# 220_small.net
KiCad netlist of a schematic drawn in Altium Designer
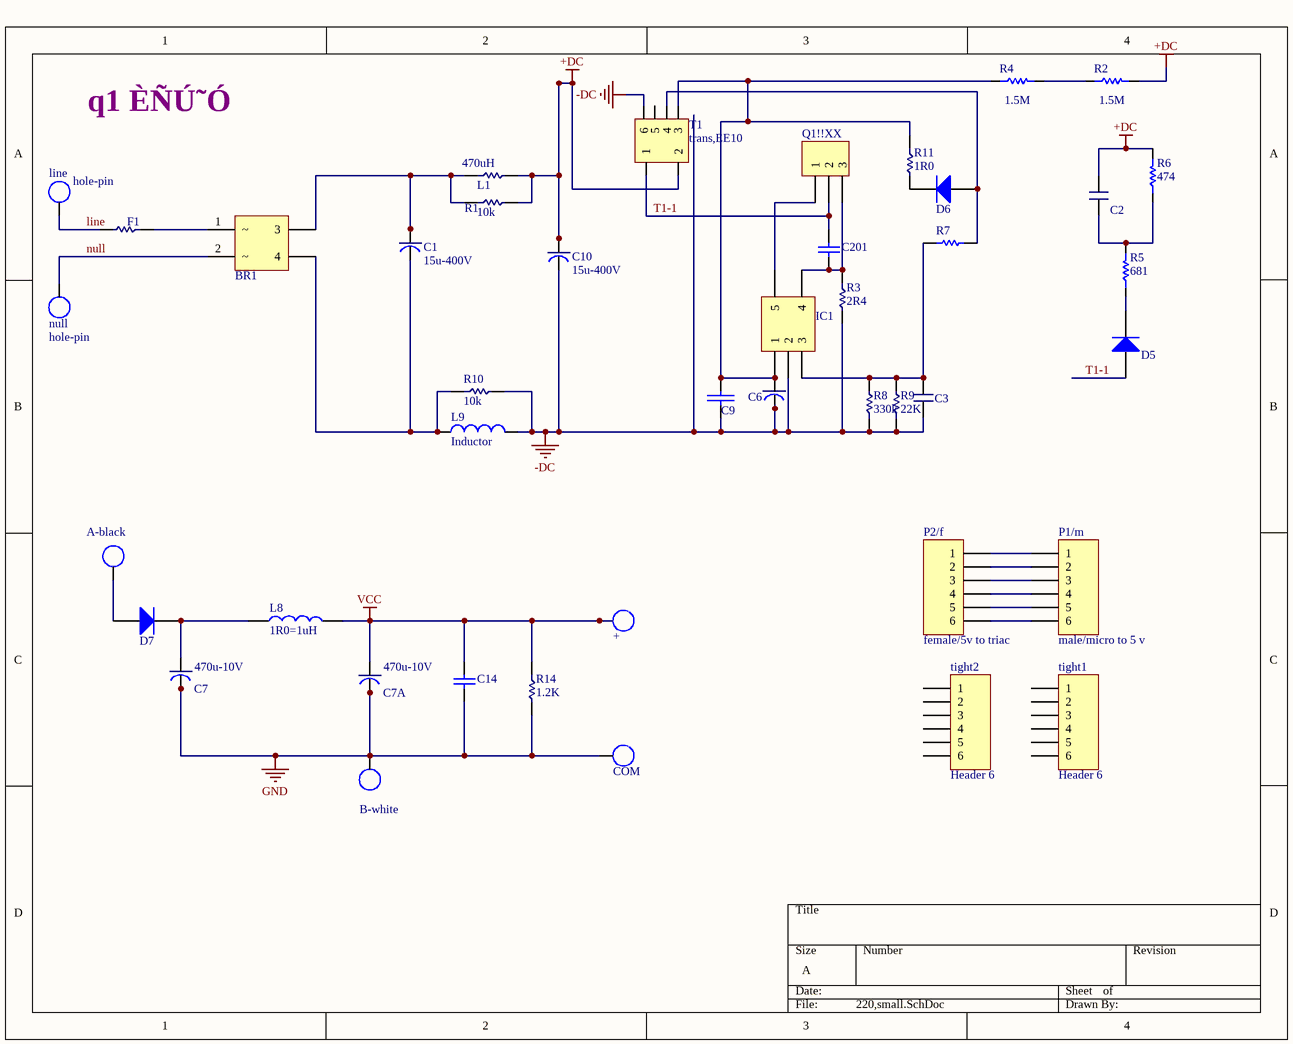
[diagram p0: 220,small.SchDoc]

(export (version "E")
  (design (tool "Eeschema 10.0.6"))
  (components
    (comp (ref "+") (value "hole-pin") (footprint "holepin") (libsource (lib "Vahid") (part "hole-pin")))
    (comp (ref "A-black")
      (value "hole-pin")
      (footprint "holepin")
      (libsource (lib "Vahid") (part "hole-pin"))
    )
    (comp (ref "B-white")
      (value "hole-pin")
      (footprint "holepin")
      (libsource (lib "Vahid") (part "hole-pin"))
    )
    (comp (ref "BR1") (value "Bridge") (footprint "MB108") (libsource (lib "VAHID LIB") (part "Bridge")))
    (comp (ref "C1") (value "15u-400V") (footprint "15u-400V") (libsource (lib "") (part "Cap Pol_1")))
    (comp (ref "C2") (value "CAP") (footprint "805") (libsource (lib "KAZEM_Library") (part "C")))
    (comp (ref "C3") (value "CAP") (footprint "805") (libsource (lib "KAZEM_Library") (part "C")))
    (comp (ref "C6")
      (value "cap-47u-50V")
      (footprint "cap47")
      (description "cap-10u-50V")
      (libsource (lib "Vahid") (part "cap"))
    )
    (comp (ref "C7") (value "470u-10V") (footprint "470u-10V") (libsource (lib "VAHID LIB") (part "Cap Pol")))
    (comp (ref "C7A")
      (value "470u-10V")
      (footprint "470u-10V")
      (libsource (lib "VAHID LIB") (part "Cap Pol"))
    )
    (comp (ref "C9")
      (value "~")
      (footprint "SMD_CAP_0805")
      (description "Bipolar Capacitor")
      (fields (field (name "VOLTAGE") "100V") (field (name "DESIGNER") "Saeid Jorablo"))
      (libsource (lib "My Library") (part "Cap-Bipolar"))
    )
    (comp (ref "C10")
      (value "15u-400V")
      (footprint "15u-400V")
      (libsource (lib "VAHID LIB") (part "Cap Pol"))
    )
    (comp (ref "C14")
      (value "Cap Semi")
      (footprint "1608[0603]")
      (description "Capacitor (Semiconductor SIM Model)")
      (fields (field (name "PUBLISHER") "Altium Limited"))
      (libsource (lib "Miscellaneous Devices") (part "Cap Semi"))
    )
    (comp (ref "C201")
      (value "Cap Semi")
      (footprint "C1206")
      (description "Capacitor (Semiconductor SIM Model)")
      (fields (field (name "PUBLISHER") "Altium Limited"))
      (libsource (lib "Miscellaneous Devices") (part "Cap Semi"))
    )
    (comp (ref "COM") (value "hole-pin") (footprint "holepin") (libsource (lib "Vahid") (part "hole-pin")))
    (comp (ref "D5")
      (value "diode")
      (footprint "diode")
      (description "diode istade")
      (libsource (lib "Vahid") (part "diode"))
    )
    (comp (ref "D6")
      (value "diode")
      (footprint "diode")
      (description "diode istade")
      (libsource (lib "Vahid") (part "diode"))
    )
    (comp (ref "D7") (value "Diode") (footprint "SB340s") (libsource (lib "VAHID LIB") (part "Diode")))
    (comp (ref "F1")
      (value "fuse-R")
      (footprint "fuse_r")
      (description "ohmic fuse")
      (libsource (lib "Vahid") (part "fuse"))
    )
    (comp (ref "IC1")
      (value "Ic in sw supply small(1A17?)")
      (footprint "SOT23-5AM")
      (libsource (lib "VAHID LIB") (part "IC,(1A17?)"))
    )
    (comp (ref "L1")
      (value "470uH")
      (footprint "fuse_r")
      (description "ohmic fuse")
      (libsource (lib "Vahid") (part "fuse"))
    )
    (comp (ref "L8") (value "1R0=1uH") (footprint "self") (libsource (lib "VAHID LIB") (part "self")))
    (comp (ref "L9")
      (value "Inductor")
      (footprint "INDC3216")
      (fields (field (name "PUBLISHER") "Altium Limited"))
      (libsource (lib "Miscellaneous Devices") (part "Inductor"))
    )
    (comp (ref "line")
      (value "hole-pin")
      (footprint "hole-pin")
      (libsource (lib "VAHID LIB") (part "hole-pin"))
    )
    (comp (ref "null")
      (value "hole-pin")
      (footprint "hole-pin")
      (libsource (lib "VAHID LIB") (part "hole-pin"))
    )
    (comp (ref "P1/m")
      (value "male/micro to 5 v")
      (footprint "HDR1X6")
      (description "Header, 6-Pin")
      (fields (field (name "PUBLISHER") "Altium Limited"))
      (libsource (lib "Miscellaneous Connectors") (part "Header 6"))
    )
    (comp (ref "P2/f")
      (value "female/5v to triac")
      (footprint "HDR1X6")
      (description "Header, 6-Pin")
      (fields (field (name "PUBLISHER") "Altium Limited"))
      (libsource (lib "") (part "Header 6_1"))
    )
    (comp (ref "Q1!!XX") (value "Q") (footprint "Q") (libsource (lib "VAHID LIB") (part "Q")))
    (comp (ref "R1")
      (value "10k")
      (footprint "805")
      (fields (field (name "Comment") "RES"))
      (libsource (lib "KAZEM_Library") (part "R"))
    )
    (comp (ref "R2")
      (value "1.5M")
      (footprint "RES 1206 (3216X08L)")
      (description "Resistor")
      (libsource (lib "My Library") (part "Resistor"))
    )
    (comp (ref "R3")
      (value "2R4")
      (footprint "805")
      (fields (field (name "Comment") "RES"))
      (libsource (lib "KAZEM_Library") (part "R"))
    )
    (comp (ref "R4")
      (value "1.5M")
      (footprint "RES 1206 (3216X08L)")
      (description "Resistor")
      (libsource (lib "My Library") (part "Resistor"))
    )
    (comp (ref "R5")
      (value "681")
      (footprint "RES 1206 (3216X08L)")
      (description "Resistor")
      (libsource (lib "My Library") (part "Resistor"))
    )
    (comp (ref "R6")
      (value "474")
      (footprint "RES 1206 (3216X08L)")
      (description "Resistor")
      (libsource (lib "My Library") (part "Resistor"))
    )
    (comp (ref "R7")
      (value "Res1")
      (footprint "AXIAL-0.3")
      (description "Resistor")
      (fields (field (name "PUBLISHER") "Altium Limited"))
      (libsource (lib "Miscellaneous Devices") (part "Res1"))
    )
    (comp (ref "R8")
      (value "330k")
      (footprint "805")
      (fields (field (name "Comment") "RES"))
      (libsource (lib "KAZEM_Library") (part "R"))
    )
    (comp (ref "R9")
      (value "22K")
      (footprint "805")
      (fields (field (name "Comment") "RES"))
      (libsource (lib "KAZEM_Library") (part "R"))
    )
    (comp (ref "R10")
      (value "10k")
      (footprint "805")
      (fields (field (name "Comment") "RES"))
      (libsource (lib "KAZEM_Library") (part "R"))
    )
    (comp (ref "R11")
      (value "1R0")
      (footprint "805")
      (fields (field (name "Comment") "RES"))
      (libsource (lib "KAZEM_Library") (part "R"))
    )
    (comp (ref "R14")
      (value "1.2K")
      (footprint "805")
      (fields (field (name "Comment") "RES"))
      (libsource (lib "KAZEM_Library") (part "R"))
    )
    (comp (ref "T1")
      (value "trans,EE10")
      (footprint "trans,EE10")
      (libsource (lib "VAHID LIB") (part "trans,EE10"))
    )
    (comp (ref "tight1")
      (value "Header 6")
      (footprint "HDR1X6")
      (description "Header, 6-Pin")
      (fields (field (name "PUBLISHER") "Altium Limited"))
      (libsource (lib "Miscellaneous Connectors") (part "Header 6"))
    )
    (comp (ref "tight2")
      (value "Header 6")
      (footprint "HDR1X6")
      (description "Header, 6-Pin")
      (fields (field (name "PUBLISHER") "Altium Limited"))
      (libsource (lib "Miscellaneous Connectors") (part "Header 6"))
    )
  )
  (nets
    (net (code "1") (name "+DC") (class "Default")
      (node (ref "C10") (pin "1") (pinfunction "1_1") (pintype "passive"))
      (node (ref "C2") (pin "2") (pinfunction "2_2") (pintype "passive"))
      (node (ref "L1") (pin "2") (pinfunction "2_2") (pintype "passive"))
      (node (ref "R1") (pin "2") (pinfunction "2_2") (pintype "passive"))
      (node (ref "R2") (pin "2") (pinfunction "2_2") (pintype "passive"))
      (node (ref "R6") (pin "2") (pinfunction "2_2") (pintype "passive"))
      (node (ref "T1") (pin "2") (pinfunction "2_2") (pintype "passive"))
    )
    (net (code "2") (name "-DC") (class "Default")
      (node (ref "C10") (pin "2") (pinfunction "2_2") (pintype "passive"))
      (node (ref "C3") (pin "2") (pinfunction "2_2") (pintype "passive"))
      (node (ref "C6") (pin "2") (pinfunction "2_2") (pintype "passive"))
      (node (ref "C9") (pin "2") (pinfunction "-_2") (pintype "passive"))
      (node (ref "IC1") (pin "2") (pinfunction "2_2") (pintype "passive"))
      (node (ref "L9") (pin "2") (pinfunction "2_2") (pintype "passive"))
      (node (ref "R10") (pin "2") (pinfunction "2_2") (pintype "passive"))
      (node (ref "R3") (pin "2") (pinfunction "2_2") (pintype "passive"))
      (node (ref "R8") (pin "1") (pinfunction "1_1") (pintype "passive"))
      (node (ref "R9") (pin "1") (pinfunction "1_1") (pintype "passive"))
      (node (ref "T1") (pin "6") (pinfunction "6_6") (pintype "passive"))
    )
    (net (code "3") (name "/T1-1") (class "Default")
      (node (ref "C201") (pin "2") (pinfunction "2_2") (pintype "passive"))
      (node (ref "D5") (pin "1") (pinfunction "1_1") (pintype "passive"))
      (node (ref "Q1!!XX") (pin "2") (pinfunction "2_2") (pintype "passive"))
      (node (ref "T1") (pin "1") (pinfunction "1_1") (pintype "passive"))
    )
    (net (code "4") (name "/line") (class "Default")
      (node (ref "F1") (pin "2") (pinfunction "2_2") (pintype "passive"))
      (node (ref "line") (pin "0") (pinfunction "0_0") (pintype "passive"))
    )
    (net (code "5") (name "/null") (class "Default")
      (node (ref "BR1") (pin "2") (pinfunction "~_2") (pintype "passive"))
      (node (ref "null") (pin "0") (pinfunction "0_0") (pintype "passive"))
    )
    (net (code "6") (name "GND") (class "Default")
      (node (ref "B-white") (pin "0") (pinfunction "0_0") (pintype "passive"))
      (node (ref "C14") (pin "1") (pinfunction "1_1") (pintype "passive"))
      (node (ref "C7") (pin "2") (pinfunction "2_2") (pintype "passive"))
      (node (ref "C7A") (pin "2") (pinfunction "2_2") (pintype "passive"))
      (node (ref "COM") (pin "0") (pinfunction "0_0") (pintype "passive"))
      (node (ref "R14") (pin "2") (pinfunction "2_2") (pintype "passive"))
    )
    (net (code "7") (name "Net-(A-black-Pad0)") (class "Default")
      (node (ref "A-black") (pin "0") (pinfunction "0_0") (pintype "passive"))
      (node (ref "D7") (pin "1") (pinfunction "1_1") (pintype "passive"))
    )
    (net (code "8") (name "Net-(BR1-Pad3)") (class "Default")
      (node (ref "BR1") (pin "3") (pinfunction "3_3") (pintype "passive"))
      (node (ref "C1") (pin "1") (pinfunction "1_1") (pintype "passive"))
      (node (ref "L1") (pin "1") (pinfunction "1_1") (pintype "passive"))
      (node (ref "R1") (pin "1") (pinfunction "1_1") (pintype "passive"))
    )
    (net (code "9") (name "Net-(BR1-Pad4)") (class "Default")
      (node (ref "BR1") (pin "4") (pinfunction "4_4") (pintype "passive"))
      (node (ref "C1") (pin "2") (pinfunction "2_2") (pintype "passive"))
      (node (ref "L9") (pin "1") (pinfunction "1_1") (pintype "passive"))
      (node (ref "R10") (pin "1") (pinfunction "1_1") (pintype "passive"))
    )
    (net (code "10") (name "Net-(BR1-~-Pad1)") (class "Default")
      (node (ref "BR1") (pin "1") (pinfunction "~_1") (pintype "passive"))
      (node (ref "F1") (pin "1") (pinfunction "1_1") (pintype "passive"))
    )
    (net (code "11") (name "Net-(C2-Pad1)") (class "Default")
      (node (ref "C2") (pin "1") (pinfunction "1_1") (pintype "passive"))
      (node (ref "R5") (pin "2") (pinfunction "2_2") (pintype "passive"))
      (node (ref "R6") (pin "1") (pinfunction "1_1") (pintype "passive"))
    )
    (net (code "12") (name "Net-(C3-Pad1)") (class "Default")
      (node (ref "C3") (pin "1") (pinfunction "1_1") (pintype "passive"))
      (node (ref "IC1") (pin "3") (pinfunction "3_3") (pintype "passive"))
      (node (ref "R7") (pin "2") (pinfunction "2_2") (pintype "passive"))
      (node (ref "R8") (pin "2") (pinfunction "2_2") (pintype "passive"))
      (node (ref "R9") (pin "2") (pinfunction "2_2") (pintype "passive"))
    )
    (net (code "13") (name "Net-(C7-Pad1)") (class "Default")
      (node (ref "C7") (pin "1") (pinfunction "1_1") (pintype "passive"))
      (node (ref "D7") (pin "2") (pinfunction "2_2") (pintype "passive"))
      (node (ref "L8") (pin "1") (pinfunction "1_1") (pintype "passive"))
    )
    (net (code "14") (name "Net-(C9-+)") (class "Default")
      (node (ref "C6") (pin "1") (pinfunction "1_1") (pintype "passive"))
      (node (ref "C9") (pin "1") (pinfunction "+_1") (pintype "passive"))
      (node (ref "IC1") (pin "1") (pinfunction "1_1") (pintype "passive"))
      (node (ref "R11") (pin "1") (pinfunction "1_1") (pintype "passive"))
      (node (ref "R4") (pin "1") (pinfunction "1_1") (pintype "passive"))
      (node (ref "T1") (pin "3") (pinfunction "3_3") (pintype "passive"))
    )
    (net (code "15") (name "Net-(C201-Pad1)") (class "Default")
      (node (ref "C201") (pin "1") (pinfunction "1_1") (pintype "passive"))
      (node (ref "IC1") (pin "4") (pinfunction "4_4") (pintype "passive"))
      (node (ref "Q1!!XX") (pin "3") (pinfunction "3_3") (pintype "passive"))
      (node (ref "R3") (pin "1") (pinfunction "1_1") (pintype "passive"))
    )
    (net (code "16") (name "Net-(D5-Pad2)") (class "Default")
      (node (ref "D5") (pin "2") (pinfunction "2_2") (pintype "passive"))
      (node (ref "R5") (pin "1") (pinfunction "1_1") (pintype "passive"))
    )
    (net (code "17") (name "Net-(D6-Pad1)") (class "Default")
      (node (ref "D6") (pin "1") (pinfunction "1_1") (pintype "passive"))
      (node (ref "R7") (pin "1") (pinfunction "1_1") (pintype "passive"))
      (node (ref "T1") (pin "4") (pinfunction "4_4") (pintype "passive"))
    )
    (net (code "18") (name "Net-(D6-Pad2)") (class "Default")
      (node (ref "D6") (pin "2") (pinfunction "2_2") (pintype "passive"))
      (node (ref "R11") (pin "2") (pinfunction "2_2") (pintype "passive"))
    )
    (net (code "19") (name "Net-(IC1-Pad5)") (class "Default")
      (node (ref "IC1") (pin "5") (pinfunction "5_5") (pintype "passive"))
      (node (ref "Q1!!XX") (pin "1") (pinfunction "1_1") (pintype "passive"))
    )
    (net (code "20") (name "Net-(P1/m-Pad1)") (class "Default")
      (node (ref "P1/m") (pin "1") (pinfunction "1_1") (pintype "passive"))
      (node (ref "P2/f") (pin "1") (pinfunction "1_1") (pintype "passive"))
    )
    (net (code "21") (name "Net-(P1/m-Pad2)") (class "Default")
      (node (ref "P1/m") (pin "2") (pinfunction "2_2") (pintype "passive"))
      (node (ref "P2/f") (pin "2") (pinfunction "2_2") (pintype "passive"))
    )
    (net (code "22") (name "Net-(P1/m-Pad3)") (class "Default")
      (node (ref "P1/m") (pin "3") (pinfunction "3_3") (pintype "passive"))
      (node (ref "P2/f") (pin "3") (pinfunction "3_3") (pintype "passive"))
    )
    (net (code "23") (name "Net-(P1/m-Pad4)") (class "Default")
      (node (ref "P1/m") (pin "4") (pinfunction "4_4") (pintype "passive"))
      (node (ref "P2/f") (pin "4") (pinfunction "4_4") (pintype "passive"))
    )
    (net (code "24") (name "Net-(P1/m-Pad5)") (class "Default")
      (node (ref "P1/m") (pin "5") (pinfunction "5_5") (pintype "passive"))
      (node (ref "P2/f") (pin "5") (pinfunction "5_5") (pintype "passive"))
    )
    (net (code "25") (name "Net-(P1/m-Pad6)") (class "Default")
      (node (ref "P1/m") (pin "6") (pinfunction "6_6") (pintype "passive"))
      (node (ref "P2/f") (pin "6") (pinfunction "6_6") (pintype "passive"))
    )
    (net (code "26") (name "Net-(R2-Pad1)") (class "Default")
      (node (ref "R2") (pin "1") (pinfunction "1_1") (pintype "passive"))
      (node (ref "R4") (pin "2") (pinfunction "2_2") (pintype "passive"))
    )
    (net (code "27") (name "VCC") (class "Default")
      (node (ref "+") (pin "0") (pinfunction "0_0") (pintype "passive"))
      (node (ref "C14") (pin "2") (pinfunction "2_2") (pintype "passive"))
      (node (ref "C7A") (pin "1") (pinfunction "1_1") (pintype "passive"))
      (node (ref "L8") (pin "2") (pinfunction "2_2") (pintype "passive"))
      (node (ref "R14") (pin "1") (pinfunction "1_1") (pintype "passive"))
    )
    (net (code "28") (name "unconnected-(T1-Pad5)") (class "Default")
      (node (ref "T1") (pin "5") (pinfunction "5_5") (pintype "passive"))
    )
    (net (code "29") (name "unconnected-(tight1-Pad1)") (class "Default")
      (node (ref "tight1") (pin "1") (pinfunction "1_1") (pintype "passive"))
    )
    (net (code "30") (name "unconnected-(tight1-Pad2)") (class "Default")
      (node (ref "tight1") (pin "2") (pinfunction "2_2") (pintype "passive"))
    )
    (net (code "31") (name "unconnected-(tight1-Pad3)") (class "Default")
      (node (ref "tight1") (pin "3") (pinfunction "3_3") (pintype "passive"))
    )
    (net (code "32") (name "unconnected-(tight1-Pad4)") (class "Default")
      (node (ref "tight1") (pin "4") (pinfunction "4_4") (pintype "passive"))
    )
    (net (code "33") (name "unconnected-(tight1-Pad5)") (class "Default")
      (node (ref "tight1") (pin "5") (pinfunction "5_5") (pintype "passive"))
    )
    (net (code "34") (name "unconnected-(tight1-Pad6)") (class "Default")
      (node (ref "tight1") (pin "6") (pinfunction "6_6") (pintype "passive"))
    )
    (net (code "35") (name "unconnected-(tight2-Pad1)") (class "Default")
      (node (ref "tight2") (pin "1") (pinfunction "1_1") (pintype "passive"))
    )
    (net (code "36") (name "unconnected-(tight2-Pad2)") (class "Default")
      (node (ref "tight2") (pin "2") (pinfunction "2_2") (pintype "passive"))
    )
    (net (code "37") (name "unconnected-(tight2-Pad3)") (class "Default")
      (node (ref "tight2") (pin "3") (pinfunction "3_3") (pintype "passive"))
    )
    (net (code "38") (name "unconnected-(tight2-Pad4)") (class "Default")
      (node (ref "tight2") (pin "4") (pinfunction "4_4") (pintype "passive"))
    )
    (net (code "39") (name "unconnected-(tight2-Pad5)") (class "Default")
      (node (ref "tight2") (pin "5") (pinfunction "5_5") (pintype "passive"))
    )
    (net (code "40") (name "unconnected-(tight2-Pad6)") (class "Default")
      (node (ref "tight2") (pin "6") (pinfunction "6_6") (pintype "passive"))
    )
  )
)
